# Schematic_Condensate-Sensor-Relay-V1.net
KiCad netlist of a schematic drawn in EasyEDA
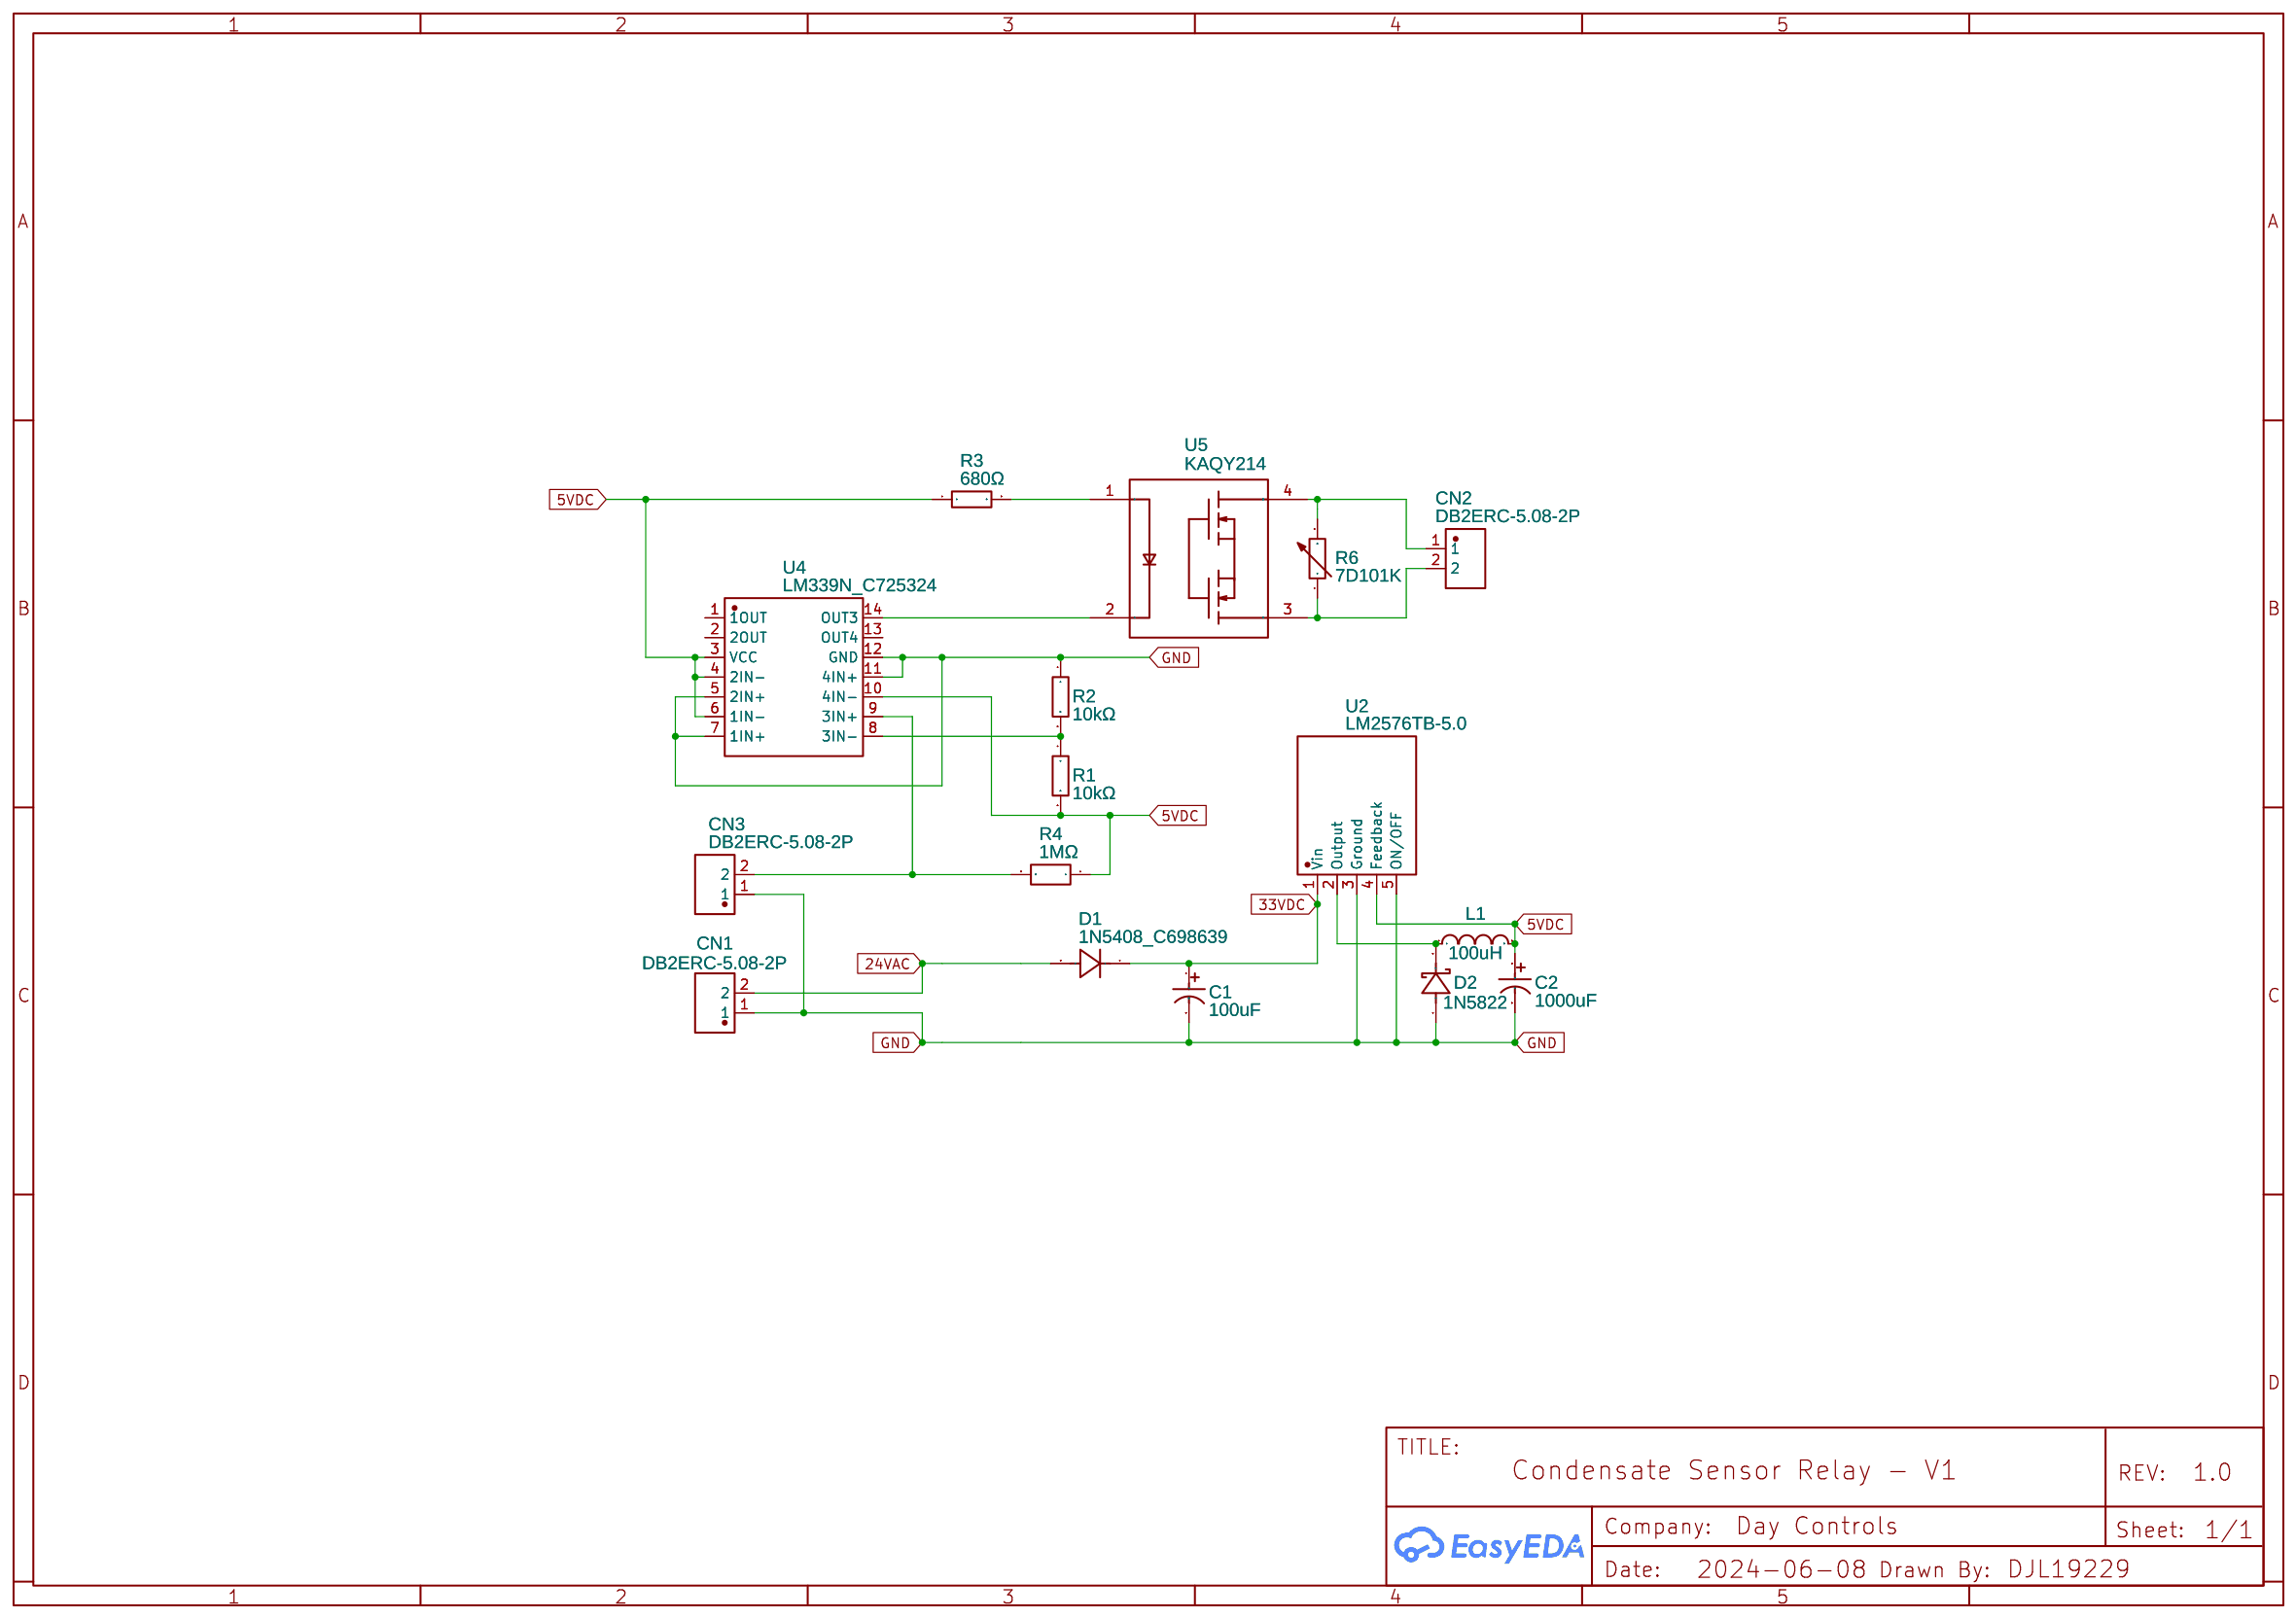
[diagram p0: schematic sheet]

(export (version "E")
  (design (tool "Eeschema 10.0.6"))
  (components
    (comp (ref "C1")
      (value "100uF")
      (fields
        (field (name "Manufacturer Part") "GR107M050F12RR0VH4FP0")
        (field (name "Manufacturer") "CX(承兴)")
      )
      (libsource (lib "") (part "100uF 50V 8*12Black high frequency"))
    )
    (comp (ref "C2")
      (value "1000uF")
      (fields
        (field (name "Manufacturer Part") "35YXJ1000M12.5X20")
        (field (name "Manufacturer") "rubycon(红宝石)")
      )
      (libsource (lib "") (part "35YXJ1000M12.5X20"))
    )
    (comp (ref "CN1")
      (value "DB2ERC-5.08-2P")
      (fields
        (field (name "Manufacturer Part") "DB2ERC-5.08-2P-GN")
        (field (name "Manufacturer") "DIBO(地博电气)")
      )
      (libsource (lib "") (part "DB2ERC-5.08-2P_1"))
    )
    (comp (ref "CN2")
      (value "DB2ERC-5.08-2P")
      (fields
        (field (name "Manufacturer Part") "DB2ERC-5.08-2P-GN")
        (field (name "Manufacturer") "DIBO(地博电气)")
      )
      (libsource (lib "") (part "DB2ERC-5.08-2P"))
    )
    (comp (ref "CN3")
      (value "DB2ERC-5.08-2P")
      (fields
        (field (name "Manufacturer Part") "DB2ERC-5.08-2P-GN")
        (field (name "Manufacturer") "DIBO(地博电气)")
      )
      (libsource (lib "") (part "DB2ERC-5.08-2P_1"))
    )
    (comp (ref "D1")
      (value "1N5408_C698639")
      (fields (field (name "Manufacturer Part") "1N5408") (field (name "Manufacturer") "YANGJIE(扬杰)"))
      (libsource (lib "") (part "1N5408_C698639"))
    )
    (comp (ref "D2")
      (value "1N5822")
      (fields (field (name "Manufacturer") "FUXINSEMI(富芯森美)"))
      (libsource (lib "") (part "1N5822_C3018526"))
    )
    (comp (ref "L1")
      (value "100uH")
      (fields (field (name "Manufacturer Part") "VLU0810-101K") (field (name "Manufacturer") "FH(风华)"))
      (libsource (lib "") (part "VLU0810-101K"))
    )
    (comp (ref "R1")
      (value "10kΩ")
      (fields (field (name "Manufacturer Part") "MF1/4W-10KΩ±1% T") (field (name "Manufacturer") "CCO(千志电子)"))
      (libsource (lib "") (part "MF1/4W-10KΩ±1% T52"))
    )
    (comp (ref "R2")
      (value "10kΩ")
      (fields (field (name "Manufacturer Part") "MF1/4W-10KΩ±1% T") (field (name "Manufacturer") "CCO(千志电子)"))
      (libsource (lib "") (part "MF1/4W-10KΩ±1% T52"))
    )
    (comp (ref "R3")
      (value "680Ω")
      (fields
        (field (name "Manufacturer Part") "MF1/2WS-680Ω±1% T")
        (field (name "Manufacturer") "CCO(千志电子)")
      )
      (libsource (lib "") (part "MF1/2WS-680Ω±1% T52"))
    )
    (comp (ref "R4")
      (value "1MΩ")
      (fields
        (field (name "Manufacturer Part") "MF1/4W-1MΩ±1%T52")
        (field (name "Manufacturer") "Huaxing Mechanical-Elec.")
      )
      (libsource (lib "") (part "MF1/4W-1MΩ±1%T52"))
    )
    (comp (ref "R6")
      (value "7D101K")
      (fields (field (name "Manufacturer") "HEL(鸿志)"))
      (libsource (lib "") (part "7D101K"))
    )
    (comp (ref "U2")
      (value "LM2576TB-5.0")
      (fields (field (name "Manufacturer") "HGSEMI(华冠)"))
      (libsource (lib "") (part "LM2576TB-5.0"))
    )
    (comp (ref "U4")
      (value "LM339N_C725324")
      (fields (field (name "Manufacturer Part") "LM339N") (field (name "Manufacturer") "HGSEMI"))
      (libsource (lib "") (part "LM339N_C725324"))
    )
    (comp (ref "U5")
      (value "KAQY214")
      (fields (field (name "Manufacturer") "cosmo(冠西)"))
      (libsource (lib "") (part "KAQY214"))
    )
  )
  (nets
    (net (code "1") (name "5VDC") (class "Default")
      (node (ref "C2") (pin "1") (pinfunction "1_1") (pintype "input"))
      (node (ref "L1") (pin "2") (pinfunction "2_2") (pintype "unspecified"))
      (node (ref "R1") (pin "2") (pinfunction "2_2") (pintype "unspecified"))
      (node (ref "R3") (pin "1") (pinfunction "1_1") (pintype "unspecified"))
      (node (ref "R4") (pin "1") (pinfunction "1_1") (pintype "unspecified"))
      (node (ref "U2") (pin "4") (pinfunction "Feedback_4") (pintype "unspecified"))
      (node (ref "U4") (pin "10") (pinfunction "4IN-_10") (pintype "unspecified"))
      (node (ref "U4") (pin "3") (pinfunction "VCC_3") (pintype "unspecified"))
      (node (ref "U4") (pin "4") (pinfunction "2IN-_4") (pintype "unspecified"))
      (node (ref "U4") (pin "6") (pinfunction "1IN-_6") (pintype "unspecified"))
    )
    (net (code "2") (name "24VAC") (class "Default")
      (node (ref "CN1") (pin "2") (pinfunction "2_2") (pintype "unspecified"))
      (node (ref "D1") (pin "2") (pinfunction "A_2") (pintype "unspecified"))
    )
    (net (code "3") (name "33VDC") (class "Default")
      (node (ref "C1") (pin "1") (pinfunction "1_1") (pintype "input"))
      (node (ref "D1") (pin "1") (pinfunction "K_1") (pintype "unspecified"))
      (node (ref "U2") (pin "1") (pinfunction "Vin_1") (pintype "unspecified"))
    )
    (net (code "4") (name "GND") (class "Default")
      (node (ref "C1") (pin "2") (pinfunction "2_2") (pintype "input"))
      (node (ref "C2") (pin "2") (pinfunction "2_2") (pintype "input"))
      (node (ref "CN1") (pin "1") (pinfunction "1_1") (pintype "unspecified"))
      (node (ref "CN3") (pin "1") (pinfunction "1_1") (pintype "unspecified"))
      (node (ref "D2") (pin "1") (pinfunction "A_1") (pintype "unspecified"))
      (node (ref "R2") (pin "1") (pinfunction "1_1") (pintype "unspecified"))
      (node (ref "U2") (pin "3") (pinfunction "Ground_3") (pintype "unspecified"))
      (node (ref "U2") (pin "5") (pinfunction "ON/OFF_5") (pintype "unspecified"))
      (node (ref "U4") (pin "11") (pinfunction "4IN+_11") (pintype "unspecified"))
      (node (ref "U4") (pin "12") (pinfunction "GND_12") (pintype "unspecified"))
      (node (ref "U4") (pin "5") (pinfunction "2IN+_5") (pintype "unspecified"))
      (node (ref "U4") (pin "7") (pinfunction "1IN+_7") (pintype "unspecified"))
    )
    (net (code "5") (name "Net-(D2-K)") (class "Default")
      (node (ref "D2") (pin "2") (pinfunction "K_2") (pintype "unspecified"))
      (node (ref "L1") (pin "1") (pinfunction "1_1") (pintype "unspecified"))
      (node (ref "U2") (pin "2") (pinfunction "Output_2") (pintype "unspecified"))
    )
    (net (code "6") (name "Net-(U4-3IN+)") (class "Default")
      (node (ref "CN3") (pin "2") (pinfunction "2_2") (pintype "unspecified"))
      (node (ref "R4") (pin "2") (pinfunction "2_2") (pintype "unspecified"))
      (node (ref "U4") (pin "9") (pinfunction "3IN+_9") (pintype "unspecified"))
    )
    (net (code "7") (name "Net-(U4-3IN-)") (class "Default")
      (node (ref "R1") (pin "1") (pinfunction "1_1") (pintype "unspecified"))
      (node (ref "R2") (pin "2") (pinfunction "2_2") (pintype "unspecified"))
      (node (ref "U4") (pin "8") (pinfunction "3IN-_8") (pintype "unspecified"))
    )
    (net (code "8") (name "Net-(U4-OUT3)") (class "Default")
      (node (ref "U4") (pin "14") (pinfunction "OUT3_14") (pintype "unspecified"))
      (node (ref "U5") (pin "2") (pinfunction "C_2") (pintype "unspecified"))
    )
    (net (code "9") (name "Net-(U5-A)") (class "Default")
      (node (ref "R3") (pin "2") (pinfunction "2_2") (pintype "unspecified"))
      (node (ref "U5") (pin "1") (pinfunction "A_1") (pintype "unspecified"))
    )
    (net (code "10") (name "Net-(U5-S)") (class "Default")
      (node (ref "CN2") (pin "1") (pinfunction "1_1") (pintype "unspecified"))
      (node (ref "R6") (pin "2") (pinfunction "2_2") (pintype "unspecified"))
      (node (ref "U5") (pin "4") (pinfunction "S_4") (pintype "unspecified"))
    )
    (net (code "11") (name "Net-(U5-S1)") (class "Default")
      (node (ref "CN2") (pin "2") (pinfunction "2_2") (pintype "unspecified"))
      (node (ref "R6") (pin "1") (pinfunction "1_1") (pintype "unspecified"))
      (node (ref "U5") (pin "3") (pinfunction "S1_3") (pintype "unspecified"))
    )
    (net (code "12") (name "unconnected-(U4-1OUT-Pad1)") (class "Default")
      (node (ref "U4") (pin "1") (pinfunction "1OUT_1") (pintype "unspecified"))
    )
    (net (code "13") (name "unconnected-(U4-2OUT-Pad2)") (class "Default")
      (node (ref "U4") (pin "2") (pinfunction "2OUT_2") (pintype "unspecified"))
    )
    (net (code "14") (name "unconnected-(U4-OUT4-Pad13)") (class "Default")
      (node (ref "U4") (pin "13") (pinfunction "OUT4_13") (pintype "unspecified"))
    )
  )
)
